# Microcontroller.net
KiCad netlist of a schematic drawn in Altium Designer
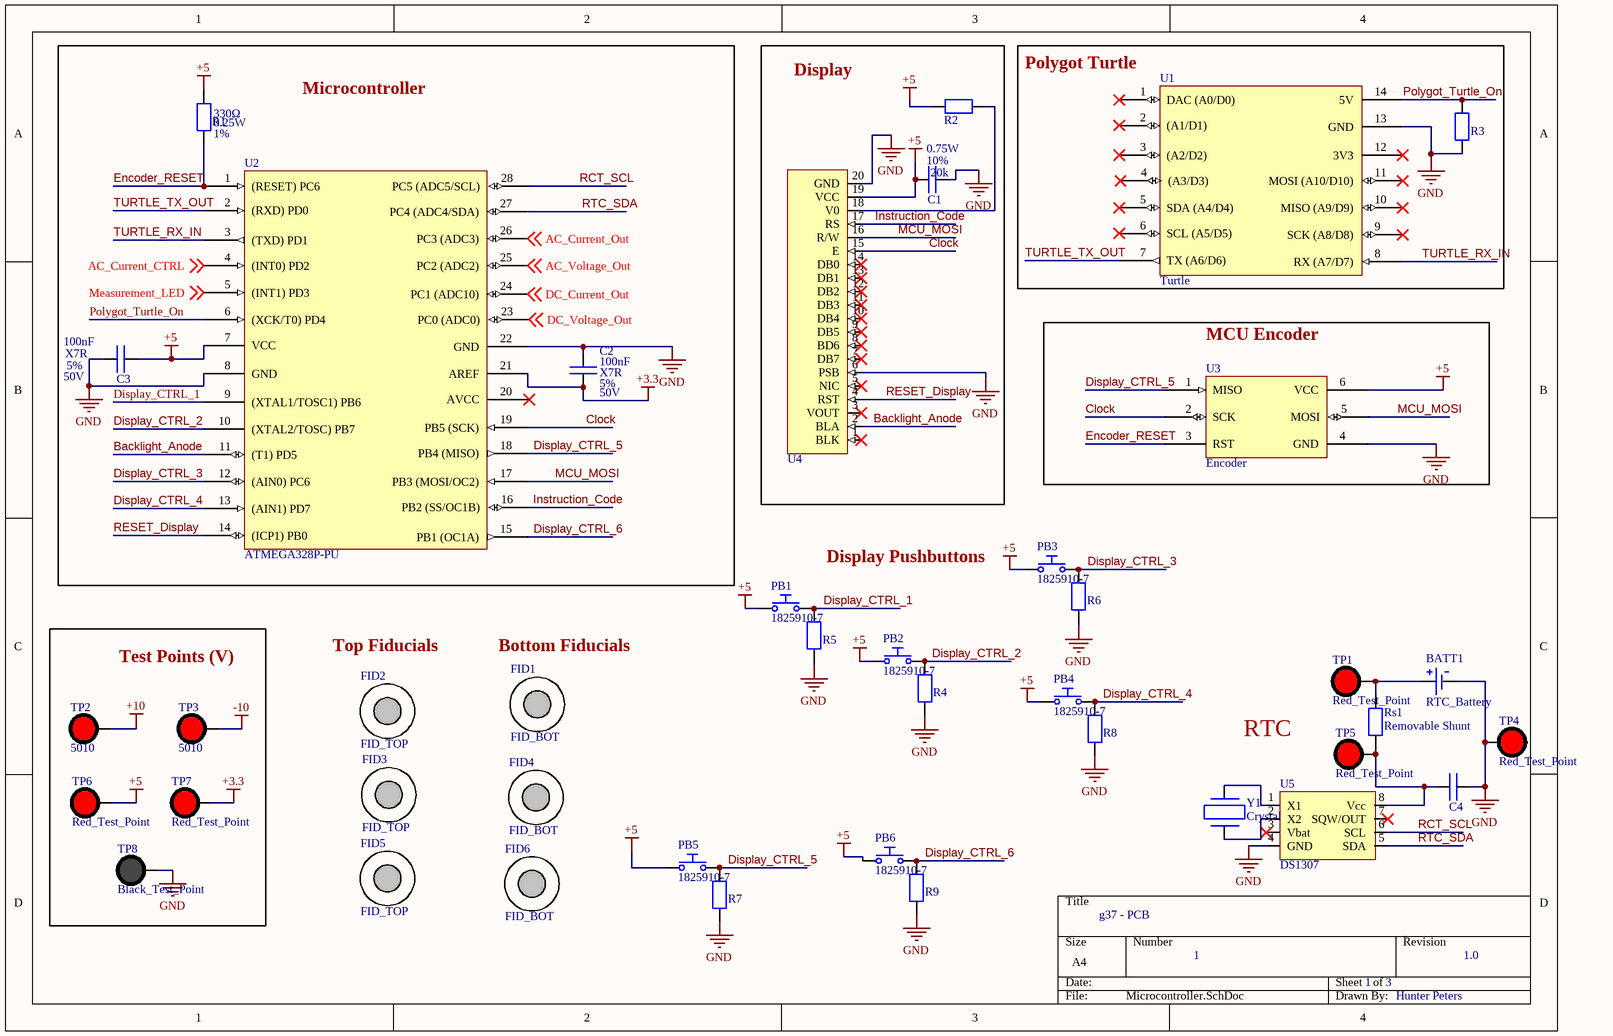
[diagram p0: Microcontroller.SchDoc]

(export (version "E")
  (design (tool "Eeschema 10.0.6"))
  (components
    (comp (ref "BATT1")
      (value "RTC_Battery")
      (footprint "Battery Holder")
      (libsource (lib "Schlib1") (part "RTC_Battery"))
    )
    (comp (ref "C1")
      (value "Capacitor")
      (footprint "Capacitor")
      (libsource (lib "Schlib1") (part "Capacitor"))
    )
    (comp (ref "C2")
      (value "Capacitor")
      (footprint "Capacitor")
      (libsource (lib "Schlib1") (part "Capacitor"))
    )
    (comp (ref "C3")
      (value "Capacitor")
      (footprint "Capacitor")
      (libsource (lib "Schlib1") (part "Capacitor"))
    )
    (comp (ref "C4")
      (value "Capacitor")
      (footprint "Capacitor")
      (libsource (lib "Schlib1") (part "Capacitor"))
    )
    (comp (ref "FID1")
      (value "FID_BOT")
      (footprint "Fiducial_TOP")
      (libsource (lib "Schlib1") (part "FID_Bottom"))
    )
    (comp (ref "FID2")
      (value "FID_TOP")
      (footprint "Fiducial_TOP")
      (libsource (lib "Schlib1") (part "FID_TOP"))
    )
    (comp (ref "FID3")
      (value "FID_TOP")
      (footprint "Fiducial_TOP")
      (libsource (lib "Schlib1") (part "FID_TOP"))
    )
    (comp (ref "FID4")
      (value "FID_BOT")
      (footprint "Fiducial_TOP")
      (libsource (lib "Schlib1") (part "FID_Bottom"))
    )
    (comp (ref "FID5")
      (value "FID_TOP")
      (footprint "Fiducial_TOP")
      (libsource (lib "Schlib1") (part "FID_TOP"))
    )
    (comp (ref "FID6")
      (value "FID_BOT")
      (footprint "Fiducial_TOP")
      (libsource (lib "Schlib1") (part "FID_Bottom"))
    )
    (comp (ref "PB1")
      (value "1825910-7")
      (footprint "Pushbutton")
      (description "Keypad Switch, 1 Switches, SPST, Momentary, 0.05A, 24VDC, 2.548N, Solder Terminal, Panel Mount")
      (fields (field (name "MANUFACTURER") "TE Connectivity"))
      (libsource (lib "Schlib1") (part "1825910-7"))
    )
    (comp (ref "PB2")
      (value "1825910-7")
      (footprint "Pushbutton")
      (description "Keypad Switch, 1 Switches, SPST, Momentary, 0.05A, 24VDC, 2.548N, Solder Terminal, Panel Mount")
      (fields (field (name "MANUFACTURER") "TE Connectivity"))
      (libsource (lib "Schlib1") (part "1825910-7"))
    )
    (comp (ref "PB3")
      (value "1825910-7")
      (footprint "Pushbutton")
      (description "Keypad Switch, 1 Switches, SPST, Momentary, 0.05A, 24VDC, 2.548N, Solder Terminal, Panel Mount")
      (fields (field (name "MANUFACTURER") "TE Connectivity"))
      (libsource (lib "Schlib1") (part "1825910-7"))
    )
    (comp (ref "PB4")
      (value "1825910-7")
      (footprint "Pushbutton")
      (description "Keypad Switch, 1 Switches, SPST, Momentary, 0.05A, 24VDC, 2.548N, Solder Terminal, Panel Mount")
      (fields (field (name "MANUFACTURER") "TE Connectivity"))
      (libsource (lib "Schlib1") (part "1825910-7"))
    )
    (comp (ref "PB5")
      (value "1825910-7")
      (footprint "Pushbutton")
      (description "Keypad Switch, 1 Switches, SPST, Momentary, 0.05A, 24VDC, 2.548N, Solder Terminal, Panel Mount")
      (fields (field (name "MANUFACTURER") "TE Connectivity"))
      (libsource (lib "Schlib1") (part "1825910-7"))
    )
    (comp (ref "PB6")
      (value "1825910-7")
      (footprint "Pushbutton")
      (description "Keypad Switch, 1 Switches, SPST, Momentary, 0.05A, 24VDC, 2.548N, Solder Terminal, Panel Mount")
      (fields (field (name "MANUFACTURER") "TE Connectivity"))
      (libsource (lib "Schlib1") (part "1825910-7"))
    )
    (comp (ref "R1") (value "Resistor") (footprint "Resistor") (libsource (lib "Schlib1") (part "Resistor")))
    (comp (ref "R2") (value "Resistor") (footprint "Resistor") (libsource (lib "Schlib1") (part "Resistor")))
    (comp (ref "R3") (value "Resistor") (footprint "Resistor") (libsource (lib "Schlib1") (part "Resistor")))
    (comp (ref "R4") (value "Resistor") (footprint "Resistor") (libsource (lib "Schlib1") (part "Resistor")))
    (comp (ref "R5") (value "Resistor") (footprint "Resistor") (libsource (lib "Schlib1") (part "Resistor")))
    (comp (ref "R6") (value "Resistor") (footprint "Resistor") (libsource (lib "Schlib1") (part "Resistor")))
    (comp (ref "R7") (value "Resistor") (footprint "Resistor") (libsource (lib "Schlib1") (part "Resistor")))
    (comp (ref "R8") (value "Resistor") (footprint "Resistor") (libsource (lib "Schlib1") (part "Resistor")))
    (comp (ref "R9") (value "Resistor") (footprint "Resistor") (libsource (lib "Schlib1") (part "Resistor")))
    (comp (ref "Rs1")
      (value "Removable Shunt")
      (footprint "Current_Shunt")
      (description "Current_Shunt")
      (libsource (lib "Schlib1") (part "Current_Test_Shunt"))
    )
    (comp (ref "TP1")
      (value "Red_Test_Point")
      (footprint "TP")
      (libsource (lib "Schlib1") (part "Red_Test_Point"))
    )
    (comp (ref "TP2") (value "5010") (footprint "TP") (libsource (lib "Schlib1") (part "Red_Test_Point")))
    (comp (ref "TP3") (value "5010") (footprint "TP") (libsource (lib "Schlib1") (part "Red_Test_Point")))
    (comp (ref "TP4")
      (value "Red_Test_Point")
      (footprint "TP")
      (libsource (lib "Schlib1") (part "Red_Test_Point"))
    )
    (comp (ref "TP5")
      (value "Red_Test_Point")
      (footprint "TP")
      (libsource (lib "Schlib1") (part "Red_Test_Point"))
    )
    (comp (ref "TP6")
      (value "Red_Test_Point")
      (footprint "TP")
      (libsource (lib "Schlib1") (part "Red_Test_Point"))
    )
    (comp (ref "TP7")
      (value "Red_Test_Point")
      (footprint "TP")
      (libsource (lib "Schlib1") (part "Red_Test_Point"))
    )
    (comp (ref "TP8")
      (value "Black_Test_Point")
      (footprint "TP")
      (libsource (lib "Schlib1") (part "Black_Test_Point"))
    )
    (comp (ref "U1")
      (value "Turtle")
      (footprint "Polygot-Turtle")
      (description "SAMD21 Microcontroller Development Board 0.0327MHz/48MHzCPU 32KB RAM 256KB Flash")
      (fields
        (field (name "MANUFACTURER") "Seeed Studio")
        (field (name "MANUFACTURER PART NUMBER") "102010328")
      )
      (libsource (lib "Schlib1") (part "102010328"))
    )
    (comp (ref "U2")
      (value "ATMEGA328P-PU")
      (footprint "ATMEGA832P\\")
      (description "Microchip - ATMEGA328P-PU - Microcontroller Mcu, 8 Bit, Atmega, 20MHZ, DIP-28")
      (fields (field (name "MANUFACTURER") "Microchip"))
      (libsource (lib "Schlib1") (part "ATMEGA328P-PU"))
    )
    (comp (ref "U3")
      (value "Encoder")
      (footprint "Encoder_No_Breakout")
      (description "Adafruit 6-Pin Avr Isp Breadboard Adapter Mini Kit ¦Adafruit 1465")
      (fields
        (field (name "MANUFACTURER") "Adafruit Industries")
        (field (name "MANUFACTURER PART NUMBER") "1465")
      )
      (libsource (lib "Schlib1") (part "1465"))
    )
    (comp (ref "U4")
      (value "LED Display")
      (footprint "LED Display")
      (libsource (lib "Schlib1") (part "Display"))
    )
    (comp (ref "U5") (value "DS1307") (footprint "Op Amp") (libsource (lib "Schlib1") (part "RTC")))
    (comp (ref "Y1") (value "Crystal") (footprint "Crystal") (libsource (lib "Schlib1") (part "Crystal")))
  )
  (nets
    (net (code "1") (name "+3.3") (class "Default")
      (node (ref "C2") (pin "1") (pinfunction "1_1") (pintype "passive"))
      (node (ref "TP7") (pin "1") (pinfunction "1_1") (pintype "passive"))
      (node (ref "U2") (pin "21") (pinfunction "AREF_21") (pintype "passive"))
    )
    (net (code "2") (name "+5") (class "Default")
      (node (ref "C1") (pin "1") (pinfunction "1_1") (pintype "passive"))
      (node (ref "C3") (pin "1") (pinfunction "1_1") (pintype "passive"))
      (node (ref "PB1") (pin "1") (pinfunction "1_1") (pintype "passive"))
      (node (ref "PB2") (pin "1") (pinfunction "1_1") (pintype "passive"))
      (node (ref "PB3") (pin "1") (pinfunction "1_1") (pintype "passive"))
      (node (ref "PB4") (pin "1") (pinfunction "1_1") (pintype "passive"))
      (node (ref "PB5") (pin "1") (pinfunction "1_1") (pintype "passive"))
      (node (ref "PB6") (pin "1") (pinfunction "1_1") (pintype "passive"))
      (node (ref "R1") (pin "1") (pinfunction "1_1") (pintype "passive"))
      (node (ref "R2") (pin "1") (pinfunction "1_1") (pintype "passive"))
      (node (ref "TP6") (pin "1") (pinfunction "1_1") (pintype "passive"))
      (node (ref "U2") (pin "7") (pinfunction "VCC_7") (pintype "power_in"))
      (node (ref "U3") (pin "6") (pinfunction "VCC_6") (pintype "power_in"))
      (node (ref "U4") (pin "19") (pinfunction "VCC_19") (pintype "power_in"))
    )
    (net (code "3") (name "+10") (class "Default")
      (node (ref "TP2") (pin "1") (pinfunction "1_1") (pintype "passive"))
    )
    (net (code "4") (name "-10") (class "Default")
      (node (ref "TP3") (pin "1") (pinfunction "1_1") (pintype "passive"))
    )
    (net (code "5") (name "/Backlight_Anode") (class "Default")
      (node (ref "U2") (pin "11") (pinfunction "(T1)_PD5_11") (pintype "bidirectional"))
      (node (ref "U4") (pin "2") (pinfunction "BLA_2") (pintype "input"))
    )
    (net (code "6") (name "/Clock") (class "Default")
      (node (ref "U2") (pin "19") (pinfunction "PB5_(SCK)_19") (pintype "input"))
      (node (ref "U3") (pin "2") (pinfunction "SCK_2") (pintype "bidirectional"))
      (node (ref "U4") (pin "15") (pinfunction "E_15") (pintype "input"))
    )
    (net (code "7") (name "/Display_CTRL_1") (class "Default")
      (node (ref "PB1") (pin "2") (pinfunction "2_2") (pintype "passive"))
      (node (ref "R5") (pin "2") (pinfunction "2_2") (pintype "passive"))
      (node (ref "U2") (pin "9") (pinfunction "(XTAL1/TOSC1)_PB6_9") (pintype "passive"))
    )
    (net (code "8") (name "/Display_CTRL_2") (class "Default")
      (node (ref "PB2") (pin "2") (pinfunction "2_2") (pintype "passive"))
      (node (ref "R4") (pin "2") (pinfunction "2_2") (pintype "passive"))
      (node (ref "U2") (pin "10") (pinfunction "(XTAL2/TOSC)_PB7_10") (pintype "passive"))
    )
    (net (code "9") (name "/Display_CTRL_3") (class "Default")
      (node (ref "PB3") (pin "2") (pinfunction "2_2") (pintype "passive"))
      (node (ref "R6") (pin "2") (pinfunction "2_2") (pintype "passive"))
      (node (ref "U2") (pin "12") (pinfunction "(AIN0)_PC6_12") (pintype "bidirectional"))
    )
    (net (code "10") (name "/Display_CTRL_4") (class "Default")
      (node (ref "PB4") (pin "2") (pinfunction "2_2") (pintype "passive"))
      (node (ref "R8") (pin "2") (pinfunction "2_2") (pintype "passive"))
      (node (ref "U2") (pin "13") (pinfunction "(AIN1)_PD7_13") (pintype "input"))
    )
    (net (code "11") (name "/Display_CTRL_5") (class "Default")
      (node (ref "PB5") (pin "2") (pinfunction "2_2") (pintype "passive"))
      (node (ref "R7") (pin "2") (pinfunction "2_2") (pintype "passive"))
      (node (ref "U2") (pin "18") (pinfunction "PB4_(MISO)_18") (pintype "output"))
      (node (ref "U3") (pin "1") (pinfunction "MISO_1") (pintype "input"))
    )
    (net (code "12") (name "/Display_CTRL_6") (class "Default")
      (node (ref "PB6") (pin "2") (pinfunction "2_2") (pintype "passive"))
      (node (ref "R9") (pin "2") (pinfunction "2_2") (pintype "passive"))
      (node (ref "U2") (pin "15") (pinfunction "PB1_(OC1A)_15") (pintype "output"))
    )
    (net (code "13") (name "/Encoder_RESET") (class "Default")
      (node (ref "R1") (pin "2") (pinfunction "2_2") (pintype "passive"))
      (node (ref "U2") (pin "1") (pinfunction "(RESET)_PC6_1") (pintype "input"))
      (node (ref "U3") (pin "3") (pinfunction "RST_3") (pintype "passive"))
    )
    (net (code "14") (name "/Instruction_Code") (class "Default")
      (node (ref "U2") (pin "16") (pinfunction "PB2_(SS/OC1B)_16") (pintype "bidirectional"))
      (node (ref "U4") (pin "17") (pinfunction "RS_17") (pintype "input"))
    )
    (net (code "15") (name "/MCU_MOSI") (class "Default")
      (node (ref "U2") (pin "17") (pinfunction "PB3_(MOSI/OC2)_17") (pintype "input"))
      (node (ref "U3") (pin "5") (pinfunction "MOSI_5") (pintype "bidirectional"))
      (node (ref "U4") (pin "16") (pinfunction "R/W_16") (pintype "bidirectional"))
    )
    (net (code "16") (name "/Polygot_Turtle_On") (class "Default")
      (node (ref "R3") (pin "2") (pinfunction "2_2") (pintype "passive"))
      (node (ref "U1") (pin "14") (pinfunction "5V_14") (pintype "power_in"))
      (node (ref "U2") (pin "6") (pinfunction "(XCK/T0)_PD4_6") (pintype "input"))
    )
    (net (code "17") (name "/RCT_SCL") (class "Default")
      (node (ref "U2") (pin "28") (pinfunction "PC5_(ADC5/SCL)_28") (pintype "bidirectional"))
      (node (ref "U5") (pin "6") (pinfunction "SCL_6") (pintype "passive"))
    )
    (net (code "18") (name "/RESET_Display") (class "Default")
      (node (ref "U2") (pin "14") (pinfunction "(ICP1)_PB0_14") (pintype "bidirectional"))
      (node (ref "U4") (pin "4") (pinfunction "RST_4") (pintype "input"))
    )
    (net (code "19") (name "/RTC_SDA") (class "Default")
      (node (ref "U2") (pin "27") (pinfunction "PC4_(ADC4/SDA)_27") (pintype "bidirectional"))
      (node (ref "U5") (pin "5") (pinfunction "SDA_5") (pintype "passive"))
    )
    (net (code "20") (name "/TURTLE_RX_IN") (class "Default")
      (node (ref "U1") (pin "8") (pinfunction "RX_(A7/D7)_8") (pintype "input"))
      (node (ref "U2") (pin "3") (pinfunction "(TXD)_PD1_3") (pintype "output"))
    )
    (net (code "21") (name "/TURTLE_TX_OUT") (class "Default")
      (node (ref "U1") (pin "7") (pinfunction "TX_(A6/D6)_7") (pintype "output"))
      (node (ref "U2") (pin "2") (pinfunction "(RXD)_PD0_2") (pintype "input"))
    )
    (net (code "22") (name "AC_Current_CTRL") (class "Default")
      (node (ref "U2") (pin "4") (pinfunction "(INT0)_PD2_4") (pintype "input"))
    )
    (net (code "23") (name "AC_Current_Out") (class "Default")
      (node (ref "U2") (pin "26") (pinfunction "PC3_(ADC3)_26") (pintype "bidirectional"))
    )
    (net (code "24") (name "AC_Voltage_Out") (class "Default")
      (node (ref "U2") (pin "25") (pinfunction "PC2_(ADC2)_25") (pintype "bidirectional"))
    )
    (net (code "25") (name "DC_Current_Out") (class "Default")
      (node (ref "U2") (pin "24") (pinfunction "PC1_(ADC10)_24") (pintype "bidirectional"))
    )
    (net (code "26") (name "DC_Voltage_Out") (class "Default")
      (node (ref "U2") (pin "23") (pinfunction "PC0_(ADC0)_23") (pintype "bidirectional"))
    )
    (net (code "27") (name "GND") (class "Default")
      (node (ref "BATT1") (pin "2") (pinfunction "2_2") (pintype "passive"))
      (node (ref "C1") (pin "2") (pinfunction "2_2") (pintype "passive"))
      (node (ref "C2") (pin "2") (pinfunction "2_2") (pintype "passive"))
      (node (ref "C3") (pin "2") (pinfunction "2_2") (pintype "passive"))
      (node (ref "C4") (pin "2") (pinfunction "2_2") (pintype "passive"))
      (node (ref "R3") (pin "1") (pinfunction "1_1") (pintype "passive"))
      (node (ref "R4") (pin "1") (pinfunction "1_1") (pintype "passive"))
      (node (ref "R5") (pin "1") (pinfunction "1_1") (pintype "passive"))
      (node (ref "R6") (pin "1") (pinfunction "1_1") (pintype "passive"))
      (node (ref "R7") (pin "1") (pinfunction "1_1") (pintype "passive"))
      (node (ref "R8") (pin "1") (pinfunction "1_1") (pintype "passive"))
      (node (ref "R9") (pin "1") (pinfunction "1_1") (pintype "passive"))
      (node (ref "TP4") (pin "1") (pinfunction "1_1") (pintype "passive"))
      (node (ref "TP8") (pin "1") (pinfunction "1_1") (pintype "passive"))
      (node (ref "U1") (pin "13") (pinfunction "GND_13") (pintype "power_in"))
      (node (ref "U2") (pin "22") (pinfunction "GND_22") (pintype "power_in"))
      (node (ref "U2") (pin "8") (pinfunction "GND_8") (pintype "power_in"))
      (node (ref "U3") (pin "4") (pinfunction "GND_4") (pintype "power_in"))
      (node (ref "U4") (pin "20") (pinfunction "GND_20") (pintype "power_in"))
      (node (ref "U4") (pin "6") (pinfunction "PSB_6") (pintype "input"))
      (node (ref "U5") (pin "4") (pinfunction "GND_4") (pintype "passive"))
    )
    (net (code "28") (name "Measurement_LED") (class "Default")
      (node (ref "U2") (pin "5") (pinfunction "(INT1)_PD3_5") (pintype "input"))
    )
    (net (code "29") (name "Net-(BATT1-Pad1)") (class "Default")
      (node (ref "BATT1") (pin "1") (pinfunction "1_1") (pintype "passive"))
      (node (ref "Rs1") (pin "2") (pinfunction "2_2") (pintype "passive"))
      (node (ref "TP1") (pin "1") (pinfunction "1_1") (pintype "passive"))
    )
    (net (code "30") (name "Net-(U4-V0)") (class "Default")
      (node (ref "R2") (pin "2") (pinfunction "2_2") (pintype "passive"))
      (node (ref "U4") (pin "18") (pinfunction "V0_18") (pintype "power_in"))
    )
    (net (code "31") (name "Net-(U5-Vcc)") (class "Default")
      (node (ref "C4") (pin "1") (pinfunction "1_1") (pintype "passive"))
      (node (ref "Rs1") (pin "1") (pinfunction "1_1") (pintype "passive"))
      (node (ref "TP5") (pin "1") (pinfunction "1_1") (pintype "passive"))
      (node (ref "U5") (pin "8") (pinfunction "Vcc_8") (pintype "passive"))
    )
    (net (code "32") (name "Net-(U5-X1)") (class "Default")
      (node (ref "U5") (pin "1") (pinfunction "X1_1") (pintype "passive"))
      (node (ref "Y1") (pin "2") (pinfunction "2_2") (pintype "passive"))
    )
    (net (code "33") (name "Net-(U5-X2)") (class "Default")
      (node (ref "U5") (pin "2") (pinfunction "X2_2") (pintype "passive"))
      (node (ref "Y1") (pin "1") (pinfunction "1_1") (pintype "passive"))
    )
    (net (code "34") (name "unconnected-(U1-(A1{slash}D1)-Pad2)") (class "Default")
      (node (ref "U1") (pin "2") (pinfunction "(A1/D1)_2") (pintype "bidirectional+no_connect"))
    )
    (net (code "35") (name "unconnected-(U1-(A2{slash}D2)-Pad3)") (class "Default")
      (node (ref "U1") (pin "3") (pinfunction "(A2/D2)_3") (pintype "bidirectional+no_connect"))
    )
    (net (code "36") (name "unconnected-(U1-(A3{slash}D3)-Pad4)") (class "Default")
      (node (ref "U1") (pin "4") (pinfunction "(A3/D3)_4") (pintype "bidirectional+no_connect"))
    )
    (net (code "37") (name "unconnected-(U1-3V3-Pad12)") (class "Default")
      (node (ref "U1") (pin "12") (pinfunction "3V3_12") (pintype "power_in+no_connect"))
    )
    (net (code "38") (name "unconnected-(U1-DAC_(A0{slash}D0)-Pad1)") (class "Default")
      (node (ref "U1") (pin "1") (pinfunction "DAC_(A0/D0)_1") (pintype "bidirectional+no_connect"))
    )
    (net (code "39") (name "unconnected-(U1-MISO_(A9{slash}D9)-Pad10)") (class "Default")
      (node (ref "U1") (pin "10") (pinfunction "MISO_(A9/D9)_10") (pintype "bidirectional+no_connect"))
    )
    (net (code "40") (name "unconnected-(U1-MOSI_(A10{slash}D10)-Pad11)") (class "Default")
      (node (ref "U1") (pin "11") (pinfunction "MOSI_(A10/D10)_11") (pintype "bidirectional+no_connect"))
    )
    (net (code "41") (name "unconnected-(U1-SCK_(A8{slash}D8)-Pad9)") (class "Default")
      (node (ref "U1") (pin "9") (pinfunction "SCK_(A8/D8)_9") (pintype "bidirectional+no_connect"))
    )
    (net (code "42") (name "unconnected-(U1-SCL_(A5{slash}D5)-Pad6)") (class "Default")
      (node (ref "U1") (pin "6") (pinfunction "SCL_(A5/D5)_6") (pintype "bidirectional+no_connect"))
    )
    (net (code "43") (name "unconnected-(U1-SDA_(A4{slash}D4)-Pad5)") (class "Default")
      (node (ref "U1") (pin "5") (pinfunction "SDA_(A4/D4)_5") (pintype "bidirectional+no_connect"))
    )
    (net (code "44") (name "unconnected-(U2-AVCC-Pad20)") (class "Default")
      (node (ref "U2") (pin "20") (pinfunction "AVCC_20") (pintype "power_in+no_connect"))
    )
    (net (code "45") (name "unconnected-(U4-BD6-Pad8)") (class "Default")
      (node (ref "U4") (pin "8") (pinfunction "BD6_8") (pintype "input+no_connect"))
    )
    (net (code "46") (name "unconnected-(U4-BLK-Pad1)") (class "Default")
      (node (ref "U4") (pin "1") (pinfunction "BLK_1") (pintype "input+no_connect"))
    )
    (net (code "47") (name "unconnected-(U4-DB0-Pad14)") (class "Default")
      (node (ref "U4") (pin "14") (pinfunction "DB0_14") (pintype "input+no_connect"))
    )
    (net (code "48") (name "unconnected-(U4-DB1-Pad13)") (class "Default")
      (node (ref "U4") (pin "13") (pinfunction "DB1_13") (pintype "input+no_connect"))
    )
    (net (code "49") (name "unconnected-(U4-DB2-Pad12)") (class "Default")
      (node (ref "U4") (pin "12") (pinfunction "DB2_12") (pintype "input+no_connect"))
    )
    (net (code "50") (name "unconnected-(U4-DB3-Pad11)") (class "Default")
      (node (ref "U4") (pin "11") (pinfunction "DB3_11") (pintype "input+no_connect"))
    )
    (net (code "51") (name "unconnected-(U4-DB4-Pad10)") (class "Default")
      (node (ref "U4") (pin "10") (pinfunction "DB4_10") (pintype "input+no_connect"))
    )
    (net (code "52") (name "unconnected-(U4-DB5-Pad9)") (class "Default")
      (node (ref "U4") (pin "9") (pinfunction "DB5_9") (pintype "input+no_connect"))
    )
    (net (code "53") (name "unconnected-(U4-DB7-Pad7)") (class "Default")
      (node (ref "U4") (pin "7") (pinfunction "DB7_7") (pintype "input+no_connect"))
    )
    (net (code "54") (name "unconnected-(U4-NIC-Pad5)") (class "Default")
      (node (ref "U4") (pin "5") (pinfunction "NIC_5") (pintype "input+no_connect"))
    )
    (net (code "55") (name "unconnected-(U4-VOUT-Pad3)") (class "Default")
      (node (ref "U4") (pin "3") (pinfunction "VOUT_3") (pintype "power_in+no_connect"))
    )
    (net (code "56") (name "unconnected-(U5-SQW{slash}OUT-Pad7)") (class "Default")
      (node (ref "U5") (pin "7") (pinfunction "SQW/OUT_7") (pintype "passive+no_connect"))
    )
    (net (code "57") (name "unconnected-(U5-Vbat-Pad3)") (class "Default")
      (node (ref "U5") (pin "3") (pinfunction "Vbat_3") (pintype "passive+no_connect"))
    )
  )
)
